# Channel.net
KiCad netlist of a schematic drawn in Altium Designer
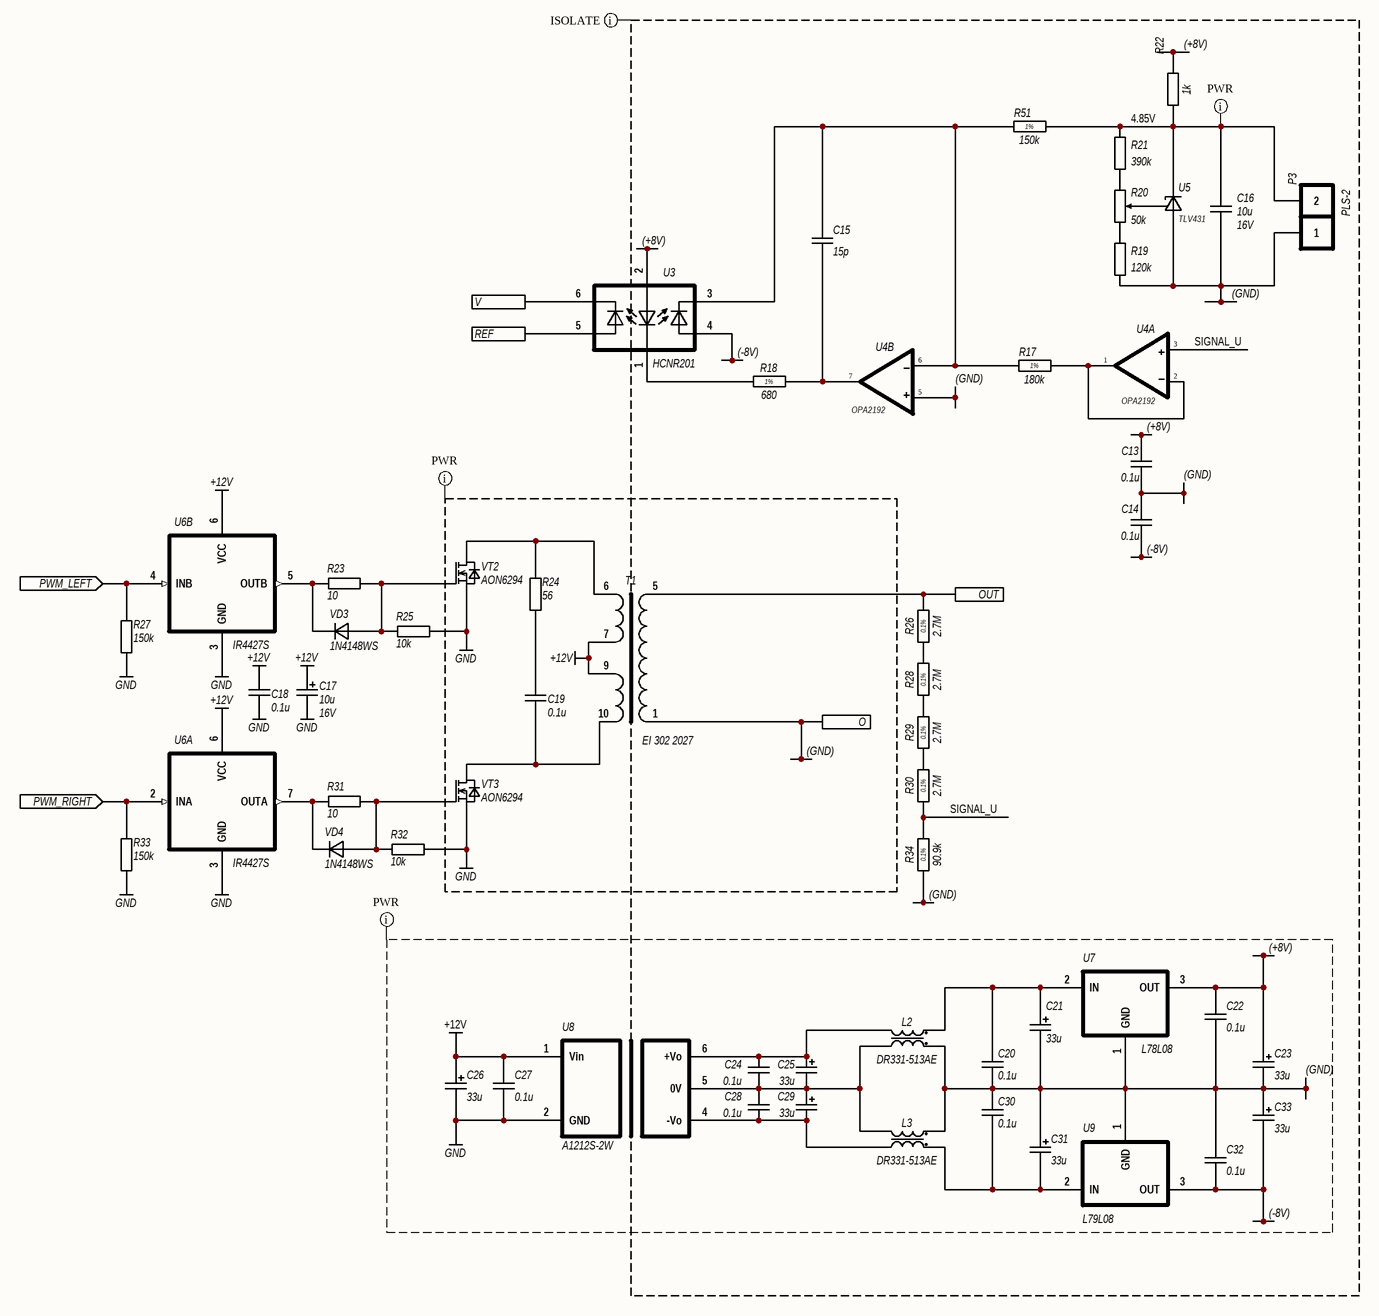
[diagram p0: Channel.SchDoc]

(export (version "E")
  (design (tool "Eeschema 10.0.6"))
  (components
    (comp (ref "C13")
      (value "0.1u")
      (footprint "C0603(1608)")
      (libsource (lib "Passive") (part "Capasitor SMD"))
    )
    (comp (ref "C14")
      (value "0.1u")
      (footprint "C0603(1608)")
      (libsource (lib "Passive") (part "Capasitor SMD"))
    )
    (comp (ref "C15")
      (value "15p")
      (footprint "C0603(1608)")
      (libsource (lib "Passive") (part "Capasitor SMD"))
    )
    (comp (ref "C16")
      (value "10u")
      (footprint "C0603(1608)")
      (fields (field (name "VOLTAGE") "16V"))
      (libsource (lib "Passive") (part "Capasitor SMD"))
    )
    (comp (ref "C17")
      (value "10u")
      (footprint "EL Case A (3216-18)")
      (description "10uF 16V Tantalum capasitor in Case-A")
      (fields (field (name "VOLTAGE") "16V"))
      (libsource (lib "Passive") (part "Capasitor TECAP"))
    )
    (comp (ref "C18")
      (value "0.1u")
      (footprint "C0603(1608)")
      (description "Multilayer Ceramic Capacitors MLCC - SMD/SMT")
      (libsource (lib "Passive") (part "Capasitor SMD"))
    )
    (comp (ref "C19")
      (value "0.1u")
      (footprint "C1206(3216)")
      (description "Multilayer Ceramic Capacitors MLCC - SMD/SMT")
      (libsource (lib "Passive") (part "Capasitor SMD"))
    )
    (comp (ref "C20")
      (value "0.1u")
      (footprint "C0603(1608)")
      (libsource (lib "Passive") (part "Capasitor SMD"))
    )
    (comp (ref "C21")
      (value "33u")
      (footprint "EL Case A (3216-18)")
      (fields (field (name "VOLTAGE") "6.3V"))
      (libsource (lib "Passive") (part "Capasitor TECAP"))
    )
    (comp (ref "C22")
      (value "0.1u")
      (footprint "C0603(1608)")
      (libsource (lib "Passive") (part "Capasitor SMD"))
    )
    (comp (ref "C23")
      (value "33u")
      (footprint "EL Case A (3216-18)")
      (fields (field (name "VOLTAGE") "6.3V"))
      (libsource (lib "Passive") (part "Capasitor TECAP"))
    )
    (comp (ref "C24")
      (value "0.1u")
      (footprint "C0603(1608)")
      (libsource (lib "Passive") (part "Capasitor SMD"))
    )
    (comp (ref "C25")
      (value "33u")
      (footprint "EL Case A (3216-18)")
      (fields (field (name "VOLTAGE") "6.3V"))
      (libsource (lib "Passive") (part "Capasitor TECAP"))
    )
    (comp (ref "C26")
      (value "33u")
      (footprint "EL Case A (3216-18)")
      (fields (field (name "VOLTAGE") "6.3V"))
      (libsource (lib "Passive") (part "Capasitor TECAP"))
    )
    (comp (ref "C27")
      (value "0.1u")
      (footprint "C0603(1608)")
      (libsource (lib "Passive") (part "Capasitor SMD"))
    )
    (comp (ref "C28")
      (value "0.1u")
      (footprint "C0603(1608)")
      (libsource (lib "Passive") (part "Capasitor SMD"))
    )
    (comp (ref "C29")
      (value "33u")
      (footprint "EL Case A (3216-18)")
      (fields (field (name "VOLTAGE") "6.3V"))
      (libsource (lib "Passive") (part "Capasitor TECAP"))
    )
    (comp (ref "C30")
      (value "0.1u")
      (footprint "C0603(1608)")
      (libsource (lib "Passive") (part "Capasitor SMD"))
    )
    (comp (ref "C31")
      (value "33u")
      (footprint "EL Case A (3216-18)")
      (fields (field (name "VOLTAGE") "6.3V"))
      (libsource (lib "Passive") (part "Capasitor TECAP"))
    )
    (comp (ref "C32")
      (value "0.1u")
      (footprint "C0603(1608)")
      (libsource (lib "Passive") (part "Capasitor SMD"))
    )
    (comp (ref "C33")
      (value "33u")
      (footprint "EL Case A (3216-18)")
      (fields (field (name "VOLTAGE") "6.3V"))
      (libsource (lib "Passive") (part "Capasitor TECAP"))
    )
    (comp (ref "L2")
      (value "DR331-513AE")
      (footprint "DR331")
      (libsource (lib "Passive") (part "Chocke Inductor"))
    )
    (comp (ref "L3")
      (value "DR331-513AE")
      (footprint "DR331")
      (libsource (lib "Passive") (part "Chocke Inductor"))
    )
    (comp (ref "P3") (value "PLS-2") (footprint "PLS-2") (libsource (lib "Connector") (part "PLS-2")))
    (comp (ref "R17")
      (value "180k")
      (footprint "R0603")
      (fields (field (name "ACCURACY") "1%"))
      (libsource (lib "Passive") (part "Resistor SMD"))
    )
    (comp (ref "R18")
      (value "680")
      (footprint "R1206")
      (fields (field (name "ACCURACY") "1%"))
      (libsource (lib "Passive") (part "Resistor SMD"))
    )
    (comp (ref "R19") (value "120k") (footprint "R0603") (libsource (lib "Passive") (part "Resistor SMD")))
    (comp (ref "R20")
      (value "50k")
      (footprint "T910W (3296W)")
      (libsource (lib "Passive") (part "Trimming Resistor"))
    )
    (comp (ref "R21") (value "390k") (footprint "R0603") (libsource (lib "Passive") (part "Resistor SMD")))
    (comp (ref "R22") (value "1k") (footprint "R0603") (libsource (lib "Passive") (part "Resistor SMD")))
    (comp (ref "R23")
      (value "10")
      (footprint "R0603")
      (description "Thick Film Resistors - SMD")
      (libsource (lib "Passive") (part "Resistor SMD"))
    )
    (comp (ref "R24")
      (value "56")
      (footprint "R2512")
      (description "Thick Film Resistors - SMD")
      (libsource (lib "Passive") (part "Resistor SMD"))
    )
    (comp (ref "R25")
      (value "10k")
      (footprint "R0603")
      (description "Thick Film Resistors - SMD")
      (libsource (lib "Passive") (part "Resistor SMD"))
    )
    (comp (ref "R26")
      (value "2.7M")
      (footprint "R2512")
      (fields (field (name "ACCURACY") "0.1%"))
      (libsource (lib "Passive") (part "Resistor SMD"))
    )
    (comp (ref "R27")
      (value "150k")
      (footprint "R0603")
      (description "Thick Film Resistors - SMD")
      (libsource (lib "Passive") (part "Resistor SMD"))
    )
    (comp (ref "R28")
      (value "2.7M")
      (footprint "R2512")
      (fields (field (name "ACCURACY") "0.1%"))
      (libsource (lib "Passive") (part "Resistor SMD"))
    )
    (comp (ref "R29")
      (value "2.7M")
      (footprint "R2512")
      (fields (field (name "ACCURACY") "0.1%"))
      (libsource (lib "Passive") (part "Resistor SMD"))
    )
    (comp (ref "R30")
      (value "2.7M")
      (footprint "R2512")
      (fields (field (name "ACCURACY") "0.1%"))
      (libsource (lib "Passive") (part "Resistor SMD"))
    )
    (comp (ref "R31")
      (value "10")
      (footprint "R0603")
      (description "Thick Film Resistors - SMD")
      (libsource (lib "Passive") (part "Resistor SMD"))
    )
    (comp (ref "R32")
      (value "10k")
      (footprint "R0603")
      (description "Thick Film Resistors - SMD")
      (libsource (lib "Passive") (part "Resistor SMD"))
    )
    (comp (ref "R33")
      (value "150k")
      (footprint "R0603")
      (description "Thick Film Resistors - SMD")
      (libsource (lib "Passive") (part "Resistor SMD"))
    )
    (comp (ref "R34")
      (value "90.9k")
      (footprint "R2512")
      (fields (field (name "ACCURACY") "0.1%"))
      (libsource (lib "Passive") (part "Resistor SMD"))
    )
    (comp (ref "R51")
      (value "150k")
      (footprint "R0603")
      (fields (field (name "ACCURACY") "1%"))
      (libsource (lib "Passive") (part "Resistor SMD"))
    )
    (comp (ref "T1") (value "~") (footprint "EI 302 2027") (libsource (lib "Transformer") (part "EI 30")))
    (comp (ref "U3") (value "HCNR201") (footprint "HCNR201") (libsource (lib "OptoCouple") (part "HCNR201")))
    (comp (ref "U4")
      (value "OPA2192")
      (footprint "SO8-150")
      (description "36-V, Precision, RRIO, Low Offset Voltage, e-trim Op Amp, 5uV 10MHz 20V/us 1mA")
      (libsource (lib "Op Amp - Comp") (part "OPA2192"))
    )
    (comp (ref "U5") (value "TLV431") (footprint "SOT23") (libsource (lib "Diode") (part "TLV431")))
    (comp (ref "U6")
      (value "IR4427S")
      (footprint "SO8-150")
      (description "Dual Low Side Driver")
      (libsource (lib "Power") (part "IR4427S"))
    )
    (comp (ref "U7") (value "L78L08") (footprint "SO8-150") (libsource (lib "Power") (part "L78Lxx")))
    (comp (ref "U8")
      (value "A1212S-2W")
      (footprint "AxxyyS-2W")
      (fields (field (name "POWER") "2"))
      (libsource (lib "Power") (part "AxxyyS-1W"))
    )
    (comp (ref "U9") (value "L79L08") (footprint "SO8-150") (libsource (lib "Power") (part "L79Lxx")))
    (comp (ref "VD3")
      (value "1N4148WS")
      (footprint "SOD323")
      (description "SOD323 100V 200mA")
      (libsource (lib "Diode") (part "1N4148WS"))
    )
    (comp (ref "VD4")
      (value "1N4148WS")
      (footprint "SOD323")
      (description "SOD323 100V 200mA")
      (libsource (lib "Diode") (part "1N4148WS"))
    )
    (comp (ref "VT2")
      (value "AON6294")
      (footprint "DFN5x6")
      (description "N-MOS 100V 10(14)mΩ 33(52)A")
      (libsource (lib "Transistor") (part "AON6294"))
    )
    (comp (ref "VT3")
      (value "AON6294")
      (footprint "DFN5x6")
      (description "N-MOS 100V 10(14)mΩ 33(52)A")
      (libsource (lib "Transistor") (part "AON6294"))
    )
  )
  (nets
    (net (code "1") (name "+12V") (class "Default")
      (node (ref "C17") (pin "1") (pinfunction "1_1") (pintype "passive"))
      (node (ref "C18") (pin "1") (pinfunction "1_1") (pintype "passive"))
      (node (ref "C26") (pin "1") (pinfunction "1_1") (pintype "passive"))
      (node (ref "C27") (pin "2") (pinfunction "2_2") (pintype "passive"))
      (node (ref "T1") (pin "7") (pinfunction "7_7") (pintype "passive"))
      (node (ref "T1") (pin "9") (pinfunction "9_9") (pintype "passive"))
      (node (ref "U6") (pin "6") (pinfunction "VCC_6") (pintype "power_in"))
      (node (ref "U8") (pin "1") (pinfunction "Vin_1") (pintype "passive"))
    )
    (net (code "2") (name "/(+8V)") (class "Default")
      (node (ref "C13") (pin "2") (pinfunction "2_2") (pintype "passive"))
      (node (ref "C22") (pin "2") (pinfunction "2_2") (pintype "passive"))
      (node (ref "C23") (pin "1") (pinfunction "1_1") (pintype "passive"))
      (node (ref "R22") (pin "1") (pinfunction "1_1") (pintype "passive"))
      (node (ref "U3") (pin "2") (pinfunction "LED_ANODE_2") (pintype "passive"))
      (node (ref "U7") (pin "3") (pinfunction "OUT_3") (pintype "power_in"))
    )
    (net (code "3") (name "/(-8V)") (class "Default")
      (node (ref "C14") (pin "1") (pinfunction "1_1") (pintype "passive"))
      (node (ref "C32") (pin "1") (pinfunction "1_1") (pintype "passive"))
      (node (ref "C33") (pin "2") (pinfunction "2_2") (pintype "passive"))
      (node (ref "U3") (pin "4") (pinfunction "PD1_ANODE_4") (pintype "passive"))
      (node (ref "U9") (pin "3") (pinfunction "OUT_3") (pintype "power_in"))
    )
    (net (code "4") (name "/(GND)") (class "Default")
      (node (ref "C13") (pin "1") (pinfunction "1_1") (pintype "passive"))
      (node (ref "C14") (pin "2") (pinfunction "2_2") (pintype "passive"))
      (node (ref "C16") (pin "1") (pinfunction "1_1") (pintype "passive"))
      (node (ref "C20") (pin "1") (pinfunction "1_1") (pintype "passive"))
      (node (ref "C21") (pin "2") (pinfunction "2_2") (pintype "passive"))
      (node (ref "C22") (pin "1") (pinfunction "1_1") (pintype "passive"))
      (node (ref "C23") (pin "2") (pinfunction "2_2") (pintype "passive"))
      (node (ref "C30") (pin "2") (pinfunction "2_2") (pintype "passive"))
      (node (ref "C31") (pin "1") (pinfunction "1_1") (pintype "passive"))
      (node (ref "C32") (pin "2") (pinfunction "2_2") (pintype "passive"))
      (node (ref "C33") (pin "1") (pinfunction "1_1") (pintype "passive"))
      (node (ref "L2") (pin "1") (pinfunction "1_1") (pintype "passive"))
      (node (ref "L3") (pin "2") (pinfunction "2_2") (pintype "passive"))
      (node (ref "P3") (pin "1") (pinfunction "1_1") (pintype "passive"))
      (node (ref "R19") (pin "2") (pinfunction "2_2") (pintype "passive"))
      (node (ref "R34") (pin "1") (pinfunction "1_1") (pintype "passive"))
      (node (ref "T1") (pin "1") (pinfunction "1_1") (pintype "passive"))
      (node (ref "U4") (pin "5") (pinfunction "+IN_5") (pintype "passive"))
      (node (ref "U5") (pin "3") (pinfunction "A_3") (pintype "passive"))
      (node (ref "U7") (pin "1") (pinfunction "GND_1") (pintype "power_in"))
      (node (ref "U9") (pin "1") (pinfunction "GND_1") (pintype "power_in"))
    )
    (net (code "5") (name "/OUT") (class "Default")
      (node (ref "R26") (pin "2") (pinfunction "2_2") (pintype "passive"))
      (node (ref "T1") (pin "5") (pinfunction "5_5") (pintype "passive"))
    )
    (net (code "6") (name "/PWM_LEFT") (class "Default")
      (node (ref "R27") (pin "1") (pinfunction "1_1") (pintype "passive"))
      (node (ref "U6") (pin "4") (pinfunction "INB_4") (pintype "input"))
    )
    (net (code "7") (name "/PWM_RIGHT") (class "Default")
      (node (ref "R33") (pin "1") (pinfunction "1_1") (pintype "passive"))
      (node (ref "U6") (pin "2") (pinfunction "INA_2") (pintype "input"))
    )
    (net (code "8") (name "/REF") (class "Default")
      (node (ref "U3") (pin "5") (pinfunction "PD2_ANODE_5") (pintype "passive"))
    )
    (net (code "9") (name "/SIGNAL_U") (class "Default")
      (node (ref "R30") (pin "1") (pinfunction "1_1") (pintype "passive"))
      (node (ref "R34") (pin "2") (pinfunction "2_2") (pintype "passive"))
      (node (ref "U4") (pin "3") (pinfunction "+IN_3") (pintype "passive"))
    )
    (net (code "10") (name "/V") (class "Default")
      (node (ref "U3") (pin "6") (pinfunction "PD2_CATHODE_6") (pintype "passive"))
    )
    (net (code "11") (name "GND") (class "Default")
      (node (ref "C17") (pin "2") (pinfunction "2_2") (pintype "passive"))
      (node (ref "C18") (pin "2") (pinfunction "2_2") (pintype "passive"))
      (node (ref "C26") (pin "2") (pinfunction "2_2") (pintype "passive"))
      (node (ref "C27") (pin "1") (pinfunction "1_1") (pintype "passive"))
      (node (ref "R25") (pin "1") (pinfunction "1_1") (pintype "passive"))
      (node (ref "R27") (pin "2") (pinfunction "2_2") (pintype "passive"))
      (node (ref "R32") (pin "1") (pinfunction "1_1") (pintype "passive"))
      (node (ref "R33") (pin "2") (pinfunction "2_2") (pintype "passive"))
      (node (ref "U6") (pin "3") (pinfunction "GND_3") (pintype "power_in"))
      (node (ref "U8") (pin "2") (pinfunction "GND_2") (pintype "passive"))
      (node (ref "VT2") (pin "3") (pinfunction "S_3") (pintype "passive"))
      (node (ref "VT3") (pin "3") (pinfunction "S_3") (pintype "passive"))
    )
    (net (code "12") (name "Net-(C19-Pad1)") (class "Default")
      (node (ref "C19") (pin "1") (pinfunction "1_1") (pintype "passive"))
      (node (ref "R24") (pin "1") (pinfunction "1_1") (pintype "passive"))
    )
    (net (code "13") (name "Net-(R19-Pad1)") (class "Default")
      (node (ref "R19") (pin "1") (pinfunction "1_1") (pintype "passive"))
      (node (ref "R20") (pin "1") (pinfunction "1_1") (pintype "passive"))
    )
    (net (code "14") (name "Net-(R20-Pad3)") (class "Default")
      (node (ref "R20") (pin "3") (pinfunction "3_3") (pintype "passive"))
      (node (ref "R21") (pin "2") (pinfunction "2_2") (pintype "passive"))
    )
    (net (code "15") (name "Net-(R26-Pad1)") (class "Default")
      (node (ref "R26") (pin "1") (pinfunction "1_1") (pintype "passive"))
      (node (ref "R28") (pin "2") (pinfunction "2_2") (pintype "passive"))
    )
    (net (code "16") (name "Net-(R28-Pad1)") (class "Default")
      (node (ref "R28") (pin "1") (pinfunction "1_1") (pintype "passive"))
      (node (ref "R29") (pin "2") (pinfunction "2_2") (pintype "passive"))
    )
    (net (code "17") (name "Net-(R29-Pad1)") (class "Default")
      (node (ref "R29") (pin "1") (pinfunction "1_1") (pintype "passive"))
      (node (ref "R30") (pin "2") (pinfunction "2_2") (pintype "passive"))
    )
    (net (code "18") (name "Net-(U3-LED_CATHODE)") (class "Default")
      (node (ref "R18") (pin "2") (pinfunction "2_2") (pintype "passive"))
      (node (ref "U3") (pin "1") (pinfunction "LED_CATHODE_1") (pintype "passive"))
    )
    (net (code "19") (name "Net-(U3-PD1_CATHODE)") (class "Default")
      (node (ref "C15") (pin "2") (pinfunction "2_2") (pintype "passive"))
      (node (ref "R17") (pin "2") (pinfunction "2_2") (pintype "passive"))
      (node (ref "R51") (pin "2") (pinfunction "2_2") (pintype "passive"))
      (node (ref "U3") (pin "3") (pinfunction "PD1_CATHODE_3") (pintype "passive"))
      (node (ref "U4") (pin "6") (pinfunction "-IN_6") (pintype "passive"))
    )
    (net (code "20") (name "Net-(U4A--IN)") (class "Default")
      (node (ref "R17") (pin "1") (pinfunction "1_1") (pintype "passive"))
      (node (ref "U4") (pin "1") (pinfunction "OUT_1") (pintype "passive"))
      (node (ref "U4") (pin "2") (pinfunction "-IN_2") (pintype "passive"))
    )
    (net (code "21") (name "Net-(U4B-OUT)") (class "Default")
      (node (ref "C15") (pin "1") (pinfunction "1_1") (pintype "passive"))
      (node (ref "R18") (pin "1") (pinfunction "1_1") (pintype "passive"))
      (node (ref "U4") (pin "7") (pinfunction "OUT_7") (pintype "passive"))
    )
    (net (code "22") (name "Net-(U5-Adj)") (class "Default")
      (node (ref "R20") (pin "2") (pinfunction "2_2") (pintype "passive"))
      (node (ref "U5") (pin "1") (pinfunction "Adj_1") (pintype "passive"))
    )
    (net (code "23") (name "Net-(U5-K)") (class "Default")
      (node (ref "C16") (pin "2") (pinfunction "2_2") (pintype "passive"))
      (node (ref "P3") (pin "2") (pinfunction "2_2") (pintype "passive"))
      (node (ref "R21") (pin "1") (pinfunction "1_1") (pintype "passive"))
      (node (ref "R22") (pin "2") (pinfunction "2_2") (pintype "passive"))
      (node (ref "R51") (pin "1") (pinfunction "1_1") (pintype "passive"))
      (node (ref "U5") (pin "2") (pinfunction "K_2") (pintype "passive"))
    )
    (net (code "24") (name "Net-(U6A-OUTA)") (class "Default")
      (node (ref "R31") (pin "1") (pinfunction "1_1") (pintype "passive"))
      (node (ref "U6") (pin "7") (pinfunction "OUTA_7") (pintype "output"))
      (node (ref "VD4") (pin "2") (pinfunction "K_2") (pintype "passive"))
    )
    (net (code "25") (name "Net-(U6B-OUTB)") (class "Default")
      (node (ref "R23") (pin "1") (pinfunction "1_1") (pintype "passive"))
      (node (ref "U6") (pin "5") (pinfunction "OUTB_5") (pintype "output"))
      (node (ref "VD3") (pin "2") (pinfunction "K_2") (pintype "passive"))
    )
    (net (code "26") (name "Net-(U7-IN)") (class "Default")
      (node (ref "C20") (pin "2") (pinfunction "2_2") (pintype "passive"))
      (node (ref "C21") (pin "1") (pinfunction "1_1") (pintype "passive"))
      (node (ref "L2") (pin "2") (pinfunction "2_2") (pintype "passive"))
      (node (ref "U7") (pin "2") (pinfunction "IN_2") (pintype "power_in"))
    )
    (net (code "27") (name "Net-(U8-+Vo)") (class "Default")
      (node (ref "C24") (pin "2") (pinfunction "2_2") (pintype "passive"))
      (node (ref "C25") (pin "1") (pinfunction "1_1") (pintype "passive"))
      (node (ref "L2") (pin "3") (pinfunction "3_3") (pintype "passive"))
      (node (ref "U8") (pin "6") (pinfunction "+Vo_6") (pintype "passive"))
    )
    (net (code "28") (name "Net-(U8--Vo)") (class "Default")
      (node (ref "C28") (pin "1") (pinfunction "1_1") (pintype "passive"))
      (node (ref "C29") (pin "2") (pinfunction "2_2") (pintype "passive"))
      (node (ref "L3") (pin "4") (pinfunction "4_4") (pintype "passive"))
      (node (ref "U8") (pin "4") (pinfunction "-Vo_4") (pintype "passive"))
    )
    (net (code "29") (name "Net-(U8-0V)") (class "Default")
      (node (ref "C24") (pin "1") (pinfunction "1_1") (pintype "passive"))
      (node (ref "C25") (pin "2") (pinfunction "2_2") (pintype "passive"))
      (node (ref "C28") (pin "2") (pinfunction "2_2") (pintype "passive"))
      (node (ref "C29") (pin "1") (pinfunction "1_1") (pintype "passive"))
      (node (ref "L2") (pin "4") (pinfunction "4_4") (pintype "passive"))
      (node (ref "L3") (pin "3") (pinfunction "3_3") (pintype "passive"))
      (node (ref "U8") (pin "5") (pinfunction "0V_5") (pintype "passive"))
    )
    (net (code "30") (name "Net-(U9-IN)") (class "Default")
      (node (ref "C30") (pin "1") (pinfunction "1_1") (pintype "passive"))
      (node (ref "C31") (pin "2") (pinfunction "2_2") (pintype "passive"))
      (node (ref "L3") (pin "1") (pinfunction "1_1") (pintype "passive"))
      (node (ref "U9") (pin "2") (pinfunction "IN_2") (pintype "power_in"))
    )
    (net (code "31") (name "Net-(VD3-A)") (class "Default")
      (node (ref "R23") (pin "2") (pinfunction "2_2") (pintype "passive"))
      (node (ref "R25") (pin "2") (pinfunction "2_2") (pintype "passive"))
      (node (ref "VD3") (pin "1") (pinfunction "A_1") (pintype "passive"))
      (node (ref "VT2") (pin "1") (pinfunction "G_1") (pintype "passive"))
    )
    (net (code "32") (name "Net-(VD4-A)") (class "Default")
      (node (ref "R31") (pin "2") (pinfunction "2_2") (pintype "passive"))
      (node (ref "R32") (pin "2") (pinfunction "2_2") (pintype "passive"))
      (node (ref "VD4") (pin "1") (pinfunction "A_1") (pintype "passive"))
      (node (ref "VT3") (pin "1") (pinfunction "G_1") (pintype "passive"))
    )
    (net (code "33") (name "Net-(VT2-D)") (class "Default")
      (node (ref "R24") (pin "2") (pinfunction "2_2") (pintype "passive"))
      (node (ref "T1") (pin "6") (pinfunction "6_6") (pintype "passive"))
      (node (ref "VT2") (pin "2") (pinfunction "D_2") (pintype "passive"))
    )
    (net (code "34") (name "Net-(VT3-D)") (class "Default")
      (node (ref "C19") (pin "2") (pinfunction "2_2") (pintype "passive"))
      (node (ref "T1") (pin "10") (pinfunction "10_10") (pintype "passive"))
      (node (ref "VT3") (pin "2") (pinfunction "D_2") (pintype "passive"))
    )
    (net (code "35") (name "V+") (class "Default")
      (node (ref "U4") (pin "8") (pinfunction "V+_8") (pintype "power_in"))
    )
    (net (code "36") (name "V-") (class "Default")
      (node (ref "U4") (pin "4") (pinfunction "V-_4") (pintype "power_in"))
    )
  )
)
